# COOLING_FAN.net
KiCad netlist of a schematic drawn in Altium Designer
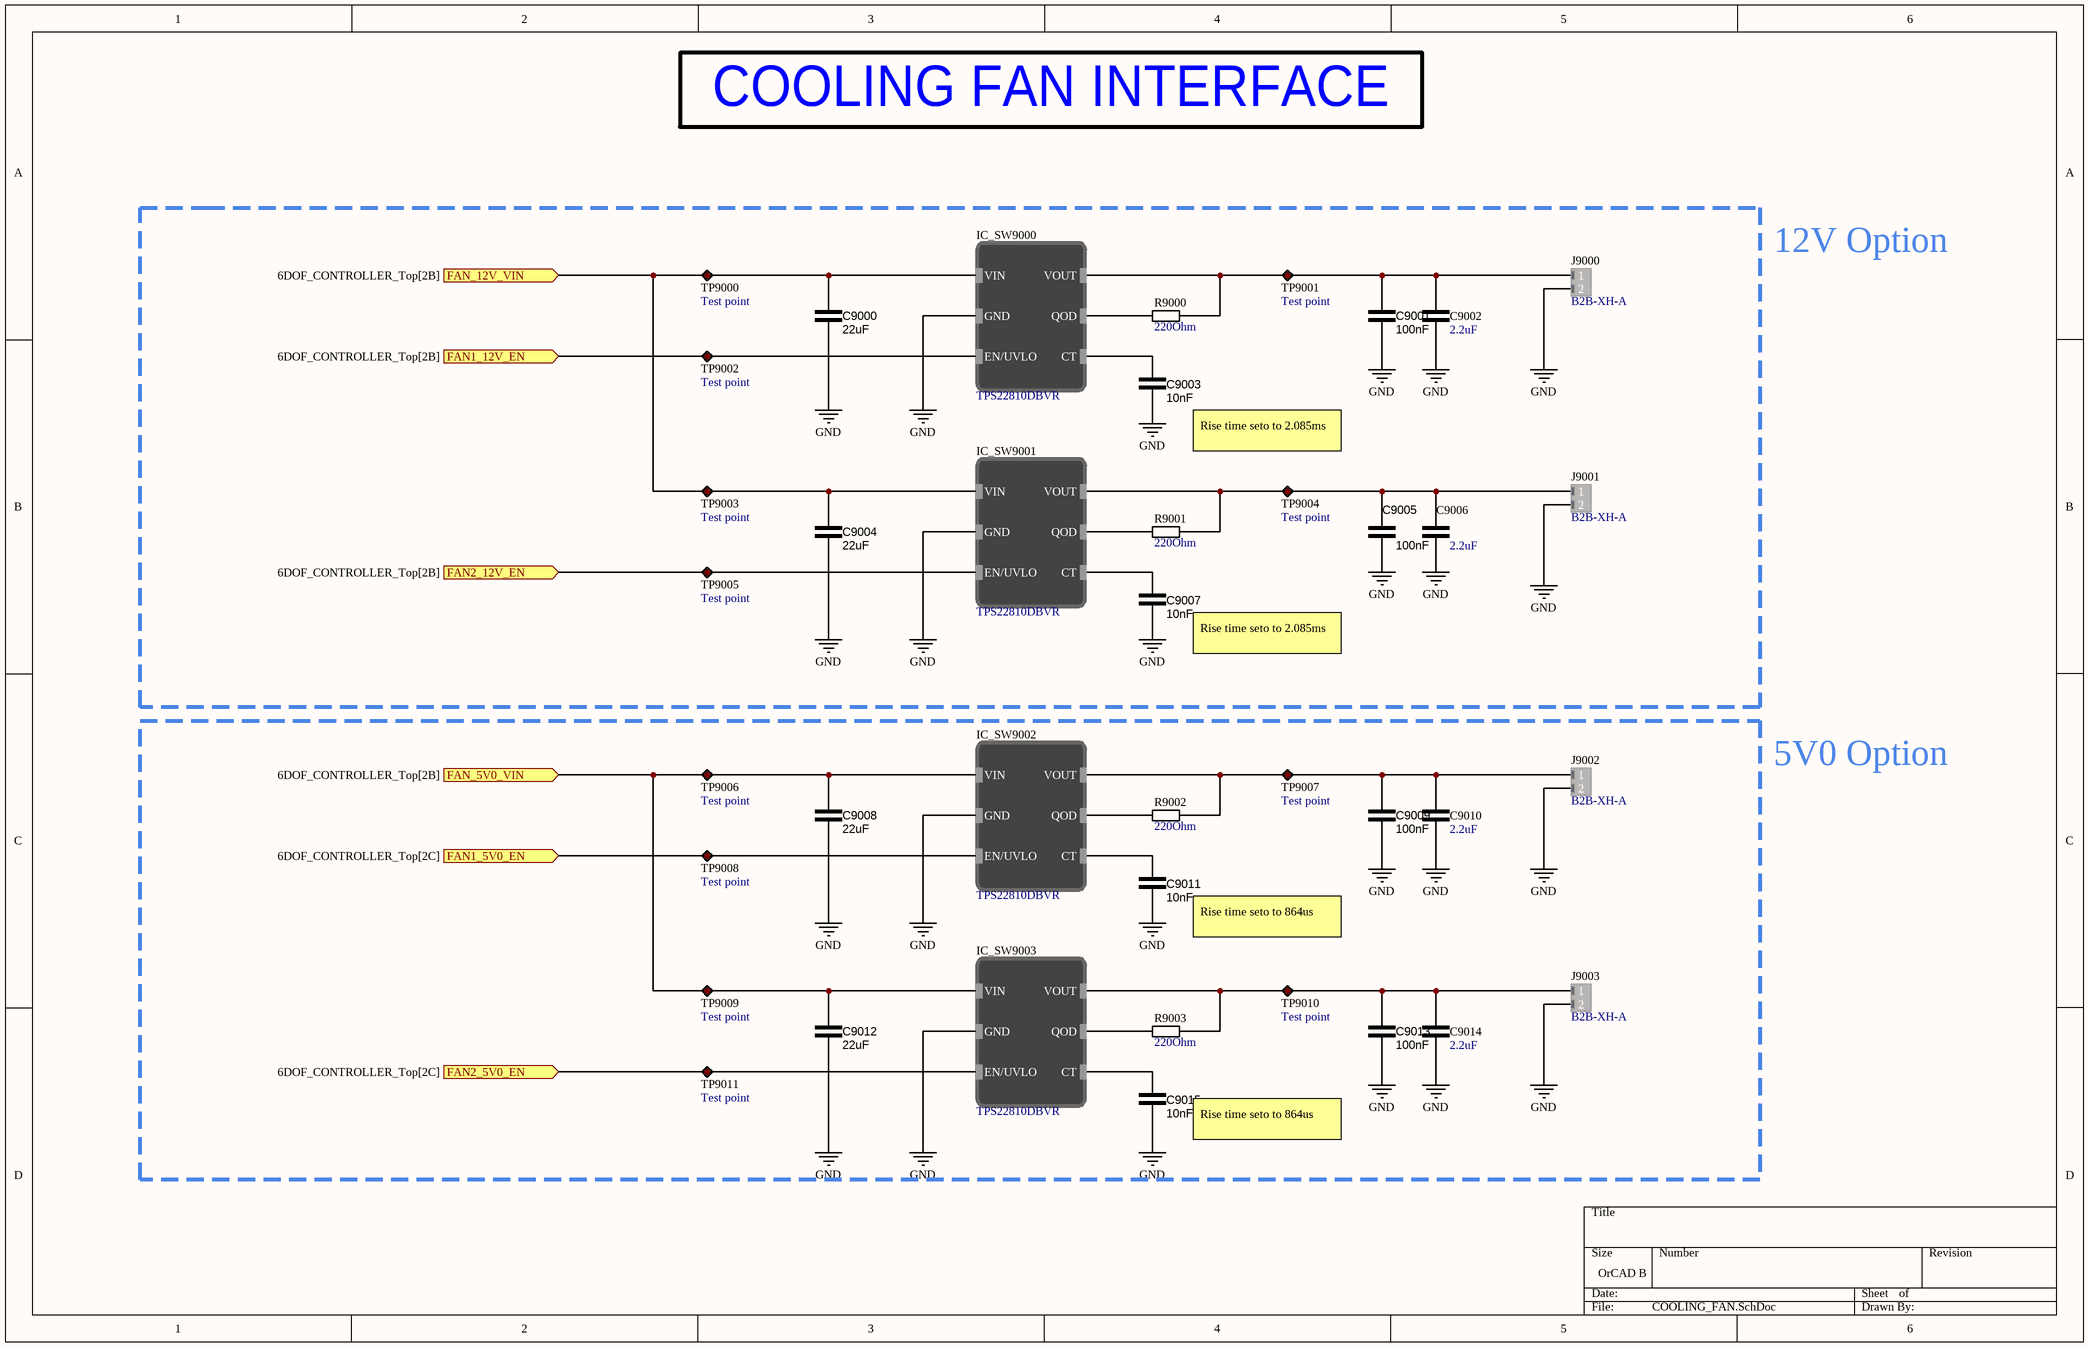
[diagram p0: COOLING_FAN.SchDoc]

(export (version "E")
  (design (tool "Eeschema 10.0.6"))
  (components
    (comp (ref "C9000")
      (value "22uF")
      (footprint "CAP_0805")
      (description "22 µF ±20% 25V Ceramic Capacitor X5R 0805 (2012 Metric)")
      (fields (field (name "DIGIKEY PART NUMBER") "445-9112-1-ND"))
      (libsource (lib "CapacitorsIntegrated") (part "C000001"))
    )
    (comp (ref "C9001")
      (value "100nF")
      (footprint "CAP_0603")
      (description "0.1 µF ±10% 25V Ceramic Capacitor X7R 0603 (1608 Metric)")
      (fields (field (name "DIGIKEY PART NUMBER") "478-KAM15AR71E104KTCT-ND"))
      (libsource (lib "CapacitorsIntegrated") (part "C000007"))
    )
    (comp (ref "C9002")
      (value "2.2uF")
      (footprint "CAP_0603")
      (description "8 pF ±0.05pF 25V Ceramic Capacitor C0G, NP0 01005 (0402 Metric)")
      (fields (field (name "DIGIKEY PART NUMBER") "490-12731-1-ND"))
      (libsource (lib "CapacitorsIntegrated") (part "C000014"))
    )
    (comp (ref "C9003")
      (value "10nF")
      (footprint "CAP_0603")
      (description "10000 pF ±20% 25V Ceramic Capacitor X7R 0603 (1608 Metric)")
      (fields (field (name "DIGIKEY PART NUMBER") "478-KGM15AR71E103MTCT-ND"))
      (libsource (lib "CapacitorsIntegrated") (part "C000005"))
    )
    (comp (ref "C9004")
      (value "22uF")
      (footprint "CAP_0805")
      (description "22 µF ±20% 25V Ceramic Capacitor X5R 0805 (2012 Metric)")
      (fields (field (name "DIGIKEY PART NUMBER") "445-9112-1-ND"))
      (libsource (lib "CapacitorsIntegrated") (part "C000001"))
    )
    (comp (ref "C9005")
      (value "100nF")
      (footprint "CAP_0603")
      (description "0.1 µF ±10% 25V Ceramic Capacitor X7R 0603 (1608 Metric)")
      (fields (field (name "DIGIKEY PART NUMBER") "478-KAM15AR71E104KTCT-ND"))
      (libsource (lib "CapacitorsIntegrated") (part "C000007"))
    )
    (comp (ref "C9006")
      (value "2.2uF")
      (footprint "CAP_0603")
      (description "8 pF ±0.05pF 25V Ceramic Capacitor C0G, NP0 01005 (0402 Metric)")
      (fields (field (name "DIGIKEY PART NUMBER") "490-12731-1-ND"))
      (libsource (lib "CapacitorsIntegrated") (part "C000014"))
    )
    (comp (ref "C9007")
      (value "10nF")
      (footprint "CAP_0603")
      (description "10000 pF ±20% 25V Ceramic Capacitor X7R 0603 (1608 Metric)")
      (fields (field (name "DIGIKEY PART NUMBER") "478-KGM15AR71E103MTCT-ND"))
      (libsource (lib "CapacitorsIntegrated") (part "C000005"))
    )
    (comp (ref "C9008")
      (value "22uF")
      (footprint "CAP_0805")
      (description "22 µF ±20% 25V Ceramic Capacitor X5R 0805 (2012 Metric)")
      (fields (field (name "DIGIKEY PART NUMBER") "445-9112-1-ND"))
      (libsource (lib "CapacitorsIntegrated") (part "C000001"))
    )
    (comp (ref "C9009")
      (value "100nF")
      (footprint "CAP_0603")
      (description "0.1 µF ±10% 25V Ceramic Capacitor X7R 0603 (1608 Metric)")
      (fields (field (name "DIGIKEY PART NUMBER") "478-KAM15AR71E104KTCT-ND"))
      (libsource (lib "CapacitorsIntegrated") (part "C000007"))
    )
    (comp (ref "C9010")
      (value "2.2uF")
      (footprint "CAP_0603")
      (description "8 pF ±0.05pF 25V Ceramic Capacitor C0G, NP0 01005 (0402 Metric)")
      (fields (field (name "DIGIKEY PART NUMBER") "490-12731-1-ND"))
      (libsource (lib "CapacitorsIntegrated") (part "C000014"))
    )
    (comp (ref "C9011")
      (value "10nF")
      (footprint "CAP_0603")
      (description "10000 pF ±20% 25V Ceramic Capacitor X7R 0603 (1608 Metric)")
      (fields (field (name "DIGIKEY PART NUMBER") "478-KGM15AR71E103MTCT-ND"))
      (libsource (lib "CapacitorsIntegrated") (part "C000005"))
    )
    (comp (ref "C9012")
      (value "22uF")
      (footprint "CAP_0805")
      (description "22 µF ±20% 25V Ceramic Capacitor X5R 0805 (2012 Metric)")
      (fields (field (name "DIGIKEY PART NUMBER") "445-9112-1-ND"))
      (libsource (lib "CapacitorsIntegrated") (part "C000001"))
    )
    (comp (ref "C9013")
      (value "100nF")
      (footprint "CAP_0603")
      (description "0.1 µF ±10% 25V Ceramic Capacitor X7R 0603 (1608 Metric)")
      (fields (field (name "DIGIKEY PART NUMBER") "478-KAM15AR71E104KTCT-ND"))
      (libsource (lib "CapacitorsIntegrated") (part "C000007"))
    )
    (comp (ref "C9014")
      (value "2.2uF")
      (footprint "CAP_0603")
      (description "8 pF ±0.05pF 25V Ceramic Capacitor C0G, NP0 01005 (0402 Metric)")
      (fields (field (name "DIGIKEY PART NUMBER") "490-12731-1-ND"))
      (libsource (lib "CapacitorsIntegrated") (part "C000014"))
    )
    (comp (ref "C9015")
      (value "10nF")
      (footprint "CAP_0603")
      (description "10000 pF ±20% 25V Ceramic Capacitor X7R 0603 (1608 Metric)")
      (fields (field (name "DIGIKEY PART NUMBER") "478-KGM15AR71E103MTCT-ND"))
      (libsource (lib "CapacitorsIntegrated") (part "C000005"))
    )
    (comp (ref "IC_SW9000")
      (value "TPS22810DBVR")
      (footprint "SOT95P280X145-6N")
      (description "Power Switch/Driver 1:1 N-Channel 2A SOT-23-6")
      (fields
        (field (name "DIGIKEY PART NUMBER") "296-45297-1-ND")
        (field (name "MOUSER PART NUMBER") "595-TPS22810DBVR")
      )
      (libsource (lib "IntegratedCircuits") (part "TPS22810"))
    )
    (comp (ref "IC_SW9001")
      (value "TPS22810DBVR")
      (footprint "SOT95P280X145-6N")
      (description "Power Switch/Driver 1:1 N-Channel 2A SOT-23-6")
      (fields
        (field (name "DIGIKEY PART NUMBER") "296-45297-1-ND")
        (field (name "MOUSER PART NUMBER") "595-TPS22810DBVR")
      )
      (libsource (lib "IntegratedCircuits") (part "TPS22810"))
    )
    (comp (ref "IC_SW9002")
      (value "TPS22810DBVR")
      (footprint "SOT95P280X145-6N")
      (description "Power Switch/Driver 1:1 N-Channel 2A SOT-23-6")
      (fields
        (field (name "DIGIKEY PART NUMBER") "296-45297-1-ND")
        (field (name "MOUSER PART NUMBER") "595-TPS22810DBVR")
      )
      (libsource (lib "IntegratedCircuits") (part "TPS22810"))
    )
    (comp (ref "IC_SW9003")
      (value "TPS22810DBVR")
      (footprint "SOT95P280X145-6N")
      (description "Power Switch/Driver 1:1 N-Channel 2A SOT-23-6")
      (fields
        (field (name "DIGIKEY PART NUMBER") "296-45297-1-ND")
        (field (name "MOUSER PART NUMBER") "595-TPS22810DBVR")
      )
      (libsource (lib "IntegratedCircuits") (part "TPS22810"))
    )
    (comp (ref "J9000")
      (value "B2B-XH-A")
      (footprint "JST_XH_2POS")
      (description "Connector Header Through Hole 2 position 0.098\" (2.50mm)")
      (fields (field (name "DIGIKEY PART NUMBER") "455-B2B-XH-A-ND"))
      (libsource (lib "ElectroMechanical") (part "00000013"))
    )
    (comp (ref "J9001")
      (value "B2B-XH-A")
      (footprint "JST_XH_2POS")
      (description "Connector Header Through Hole 2 position 0.098\" (2.50mm)")
      (fields (field (name "DIGIKEY PART NUMBER") "455-B2B-XH-A-ND"))
      (libsource (lib "ElectroMechanical") (part "00000013"))
    )
    (comp (ref "J9002")
      (value "B2B-XH-A")
      (footprint "JST_XH_2POS")
      (description "Connector Header Through Hole 2 position 0.098\" (2.50mm)")
      (fields (field (name "DIGIKEY PART NUMBER") "455-B2B-XH-A-ND"))
      (libsource (lib "ElectroMechanical") (part "00000013"))
    )
    (comp (ref "J9003")
      (value "B2B-XH-A")
      (footprint "JST_XH_2POS")
      (description "Connector Header Through Hole 2 position 0.098\" (2.50mm)")
      (fields (field (name "DIGIKEY PART NUMBER") "455-B2B-XH-A-ND"))
      (libsource (lib "ElectroMechanical") (part "00000013"))
    )
    (comp (ref "R9000")
      (value "220Ohm")
      (footprint "RES_0603")
      (description "220 Ohms ±5% 0.1W, 1/10W Chip Resistor 0603 (1608 Metric) Automotive AEC-Q200 Thick Film")
      (fields (field (name "DIGIKEY PART NUMBER") "P220GCT-ND"))
      (libsource (lib "ResistorsIntegrated") (part "R000021"))
    )
    (comp (ref "R9001")
      (value "220Ohm")
      (footprint "RES_0603")
      (description "220 Ohms ±5% 0.1W, 1/10W Chip Resistor 0603 (1608 Metric) Automotive AEC-Q200 Thick Film")
      (fields (field (name "DIGIKEY PART NUMBER") "P220GCT-ND"))
      (libsource (lib "ResistorsIntegrated") (part "R000021"))
    )
    (comp (ref "R9002")
      (value "220Ohm")
      (footprint "RES_0603")
      (description "220 Ohms ±5% 0.1W, 1/10W Chip Resistor 0603 (1608 Metric) Automotive AEC-Q200 Thick Film")
      (fields (field (name "DIGIKEY PART NUMBER") "P220GCT-ND"))
      (libsource (lib "ResistorsIntegrated") (part "R000021"))
    )
    (comp (ref "R9003")
      (value "220Ohm")
      (footprint "RES_0603")
      (description "220 Ohms ±5% 0.1W, 1/10W Chip Resistor 0603 (1608 Metric) Automotive AEC-Q200 Thick Film")
      (fields (field (name "DIGIKEY PART NUMBER") "P220GCT-ND"))
      (libsource (lib "ResistorsIntegrated") (part "R000021"))
    )
    (comp (ref "TP9000")
      (value "Test point")
      (footprint "TestPoint")
      (description "Test point 1mm")
      (libsource (lib "IntegratedCircuits") (part "TP002"))
    )
    (comp (ref "TP9001")
      (value "Test point")
      (footprint "TestPoint")
      (description "Test point 1mm")
      (libsource (lib "IntegratedCircuits") (part "TP002"))
    )
    (comp (ref "TP9002")
      (value "Test point")
      (footprint "TestPoint")
      (description "Test point 1mm")
      (libsource (lib "IntegratedCircuits") (part "TP002"))
    )
    (comp (ref "TP9003")
      (value "Test point")
      (footprint "TestPoint")
      (description "Test point 1mm")
      (libsource (lib "IntegratedCircuits") (part "TP002"))
    )
    (comp (ref "TP9004")
      (value "Test point")
      (footprint "TestPoint")
      (description "Test point 1mm")
      (libsource (lib "IntegratedCircuits") (part "TP002"))
    )
    (comp (ref "TP9005")
      (value "Test point")
      (footprint "TestPoint")
      (description "Test point 1mm")
      (libsource (lib "IntegratedCircuits") (part "TP002"))
    )
    (comp (ref "TP9006")
      (value "Test point")
      (footprint "TestPoint")
      (description "Test point 1mm")
      (libsource (lib "IntegratedCircuits") (part "TP002"))
    )
    (comp (ref "TP9007")
      (value "Test point")
      (footprint "TestPoint")
      (description "Test point 1mm")
      (libsource (lib "IntegratedCircuits") (part "TP002"))
    )
    (comp (ref "TP9008")
      (value "Test point")
      (footprint "TestPoint")
      (description "Test point 1mm")
      (libsource (lib "IntegratedCircuits") (part "TP002"))
    )
    (comp (ref "TP9009")
      (value "Test point")
      (footprint "TestPoint")
      (description "Test point 1mm")
      (libsource (lib "IntegratedCircuits") (part "TP002"))
    )
    (comp (ref "TP9010")
      (value "Test point")
      (footprint "TestPoint")
      (description "Test point 1mm")
      (libsource (lib "IntegratedCircuits") (part "TP002"))
    )
    (comp (ref "TP9011")
      (value "Test point")
      (footprint "TestPoint")
      (description "Test point 1mm")
      (libsource (lib "IntegratedCircuits") (part "TP002"))
    )
  )
  (nets
    (net (code "1") (name "/FAN1_5V0_EN") (class "Default")
      (node (ref "IC_SW9002") (pin "3") (pinfunction "EN/UVLO_3") (pintype "passive"))
      (node (ref "TP9008") (pin "1") (pinfunction "1_1") (pintype "passive"))
    )
    (net (code "2") (name "/FAN1_12V_EN") (class "Default")
      (node (ref "IC_SW9000") (pin "3") (pinfunction "EN/UVLO_3") (pintype "passive"))
      (node (ref "TP9002") (pin "1") (pinfunction "1_1") (pintype "passive"))
    )
    (net (code "3") (name "/FAN2_5V0_EN") (class "Default")
      (node (ref "IC_SW9003") (pin "3") (pinfunction "EN/UVLO_3") (pintype "passive"))
      (node (ref "TP9011") (pin "1") (pinfunction "1_1") (pintype "passive"))
    )
    (net (code "4") (name "/FAN2_12V_EN") (class "Default")
      (node (ref "IC_SW9001") (pin "3") (pinfunction "EN/UVLO_3") (pintype "passive"))
      (node (ref "TP9005") (pin "1") (pinfunction "1_1") (pintype "passive"))
    )
    (net (code "5") (name "/FAN_5V0_VIN") (class "Default")
      (node (ref "C9008") (pin "2") (pinfunction "2_2") (pintype "passive"))
      (node (ref "C9012") (pin "2") (pinfunction "2_2") (pintype "passive"))
      (node (ref "IC_SW9002") (pin "1") (pinfunction "VIN_1") (pintype "passive"))
      (node (ref "IC_SW9003") (pin "1") (pinfunction "VIN_1") (pintype "passive"))
      (node (ref "TP9006") (pin "1") (pinfunction "1_1") (pintype "passive"))
      (node (ref "TP9009") (pin "1") (pinfunction "1_1") (pintype "passive"))
    )
    (net (code "6") (name "/FAN_12V_VIN") (class "Default")
      (node (ref "C9000") (pin "2") (pinfunction "2_2") (pintype "passive"))
      (node (ref "C9004") (pin "2") (pinfunction "2_2") (pintype "passive"))
      (node (ref "IC_SW9000") (pin "1") (pinfunction "VIN_1") (pintype "passive"))
      (node (ref "IC_SW9001") (pin "1") (pinfunction "VIN_1") (pintype "passive"))
      (node (ref "TP9000") (pin "1") (pinfunction "1_1") (pintype "passive"))
      (node (ref "TP9003") (pin "1") (pinfunction "1_1") (pintype "passive"))
    )
    (net (code "7") (name "GND") (class "Default")
      (node (ref "C9000") (pin "1") (pinfunction "1_1") (pintype "passive"))
      (node (ref "C9001") (pin "2") (pinfunction "2_2") (pintype "passive"))
      (node (ref "C9002") (pin "1") (pinfunction "1_1") (pintype "passive"))
      (node (ref "C9003") (pin "1") (pinfunction "1_1") (pintype "passive"))
      (node (ref "C9004") (pin "1") (pinfunction "1_1") (pintype "passive"))
      (node (ref "C9005") (pin "2") (pinfunction "2_2") (pintype "passive"))
      (node (ref "C9006") (pin "1") (pinfunction "1_1") (pintype "passive"))
      (node (ref "C9007") (pin "1") (pinfunction "1_1") (pintype "passive"))
      (node (ref "C9008") (pin "1") (pinfunction "1_1") (pintype "passive"))
      (node (ref "C9009") (pin "2") (pinfunction "2_2") (pintype "passive"))
      (node (ref "C9010") (pin "1") (pinfunction "1_1") (pintype "passive"))
      (node (ref "C9011") (pin "1") (pinfunction "1_1") (pintype "passive"))
      (node (ref "C9012") (pin "1") (pinfunction "1_1") (pintype "passive"))
      (node (ref "C9013") (pin "2") (pinfunction "2_2") (pintype "passive"))
      (node (ref "C9014") (pin "1") (pinfunction "1_1") (pintype "passive"))
      (node (ref "C9015") (pin "1") (pinfunction "1_1") (pintype "passive"))
      (node (ref "IC_SW9000") (pin "2") (pinfunction "GND_2") (pintype "passive"))
      (node (ref "IC_SW9001") (pin "2") (pinfunction "GND_2") (pintype "passive"))
      (node (ref "IC_SW9002") (pin "2") (pinfunction "GND_2") (pintype "passive"))
      (node (ref "IC_SW9003") (pin "2") (pinfunction "GND_2") (pintype "passive"))
      (node (ref "J9000") (pin "2") (pinfunction "2_2") (pintype "passive"))
      (node (ref "J9001") (pin "2") (pinfunction "2_2") (pintype "passive"))
      (node (ref "J9002") (pin "2") (pinfunction "2_2") (pintype "passive"))
      (node (ref "J9003") (pin "2") (pinfunction "2_2") (pintype "passive"))
    )
    (net (code "8") (name "Net-(IC_SW9000-CT)") (class "Default")
      (node (ref "C9003") (pin "2") (pinfunction "2_2") (pintype "passive"))
      (node (ref "IC_SW9000") (pin "4") (pinfunction "CT_4") (pintype "passive"))
    )
    (net (code "9") (name "Net-(IC_SW9000-QOD)") (class "Default")
      (node (ref "IC_SW9000") (pin "5") (pinfunction "QOD_5") (pintype "passive"))
      (node (ref "R9000") (pin "1") (pinfunction "1_1") (pintype "passive"))
    )
    (net (code "10") (name "Net-(IC_SW9000-VOUT)") (class "Default")
      (node (ref "C9001") (pin "1") (pinfunction "1_1") (pintype "passive"))
      (node (ref "C9002") (pin "2") (pinfunction "2_2") (pintype "passive"))
      (node (ref "IC_SW9000") (pin "6") (pinfunction "VOUT_6") (pintype "passive"))
      (node (ref "J9000") (pin "1") (pinfunction "1_1") (pintype "passive"))
      (node (ref "R9000") (pin "2") (pinfunction "2_2") (pintype "passive"))
      (node (ref "TP9001") (pin "1") (pinfunction "1_1") (pintype "passive"))
    )
    (net (code "11") (name "Net-(IC_SW9001-CT)") (class "Default")
      (node (ref "C9007") (pin "2") (pinfunction "2_2") (pintype "passive"))
      (node (ref "IC_SW9001") (pin "4") (pinfunction "CT_4") (pintype "passive"))
    )
    (net (code "12") (name "Net-(IC_SW9001-QOD)") (class "Default")
      (node (ref "IC_SW9001") (pin "5") (pinfunction "QOD_5") (pintype "passive"))
      (node (ref "R9001") (pin "1") (pinfunction "1_1") (pintype "passive"))
    )
    (net (code "13") (name "Net-(IC_SW9001-VOUT)") (class "Default")
      (node (ref "C9005") (pin "1") (pinfunction "1_1") (pintype "passive"))
      (node (ref "C9006") (pin "2") (pinfunction "2_2") (pintype "passive"))
      (node (ref "IC_SW9001") (pin "6") (pinfunction "VOUT_6") (pintype "passive"))
      (node (ref "J9001") (pin "1") (pinfunction "1_1") (pintype "passive"))
      (node (ref "R9001") (pin "2") (pinfunction "2_2") (pintype "passive"))
      (node (ref "TP9004") (pin "1") (pinfunction "1_1") (pintype "passive"))
    )
    (net (code "14") (name "Net-(IC_SW9002-CT)") (class "Default")
      (node (ref "C9011") (pin "2") (pinfunction "2_2") (pintype "passive"))
      (node (ref "IC_SW9002") (pin "4") (pinfunction "CT_4") (pintype "passive"))
    )
    (net (code "15") (name "Net-(IC_SW9002-QOD)") (class "Default")
      (node (ref "IC_SW9002") (pin "5") (pinfunction "QOD_5") (pintype "passive"))
      (node (ref "R9002") (pin "1") (pinfunction "1_1") (pintype "passive"))
    )
    (net (code "16") (name "Net-(IC_SW9002-VOUT)") (class "Default")
      (node (ref "C9009") (pin "1") (pinfunction "1_1") (pintype "passive"))
      (node (ref "C9010") (pin "2") (pinfunction "2_2") (pintype "passive"))
      (node (ref "IC_SW9002") (pin "6") (pinfunction "VOUT_6") (pintype "passive"))
      (node (ref "J9002") (pin "1") (pinfunction "1_1") (pintype "passive"))
      (node (ref "R9002") (pin "2") (pinfunction "2_2") (pintype "passive"))
      (node (ref "TP9007") (pin "1") (pinfunction "1_1") (pintype "passive"))
    )
    (net (code "17") (name "Net-(IC_SW9003-CT)") (class "Default")
      (node (ref "C9015") (pin "2") (pinfunction "2_2") (pintype "passive"))
      (node (ref "IC_SW9003") (pin "4") (pinfunction "CT_4") (pintype "passive"))
    )
    (net (code "18") (name "Net-(IC_SW9003-QOD)") (class "Default")
      (node (ref "IC_SW9003") (pin "5") (pinfunction "QOD_5") (pintype "passive"))
      (node (ref "R9003") (pin "1") (pinfunction "1_1") (pintype "passive"))
    )
    (net (code "19") (name "Net-(IC_SW9003-VOUT)") (class "Default")
      (node (ref "C9013") (pin "1") (pinfunction "1_1") (pintype "passive"))
      (node (ref "C9014") (pin "2") (pinfunction "2_2") (pintype "passive"))
      (node (ref "IC_SW9003") (pin "6") (pinfunction "VOUT_6") (pintype "passive"))
      (node (ref "J9003") (pin "1") (pinfunction "1_1") (pintype "passive"))
      (node (ref "R9003") (pin "2") (pinfunction "2_2") (pintype "passive"))
      (node (ref "TP9010") (pin "1") (pinfunction "1_1") (pintype "passive"))
    )
  )
)
